# brick_i2c_gyro_l3gd20.net
KiCad netlist of a schematic drawn in EAGLE
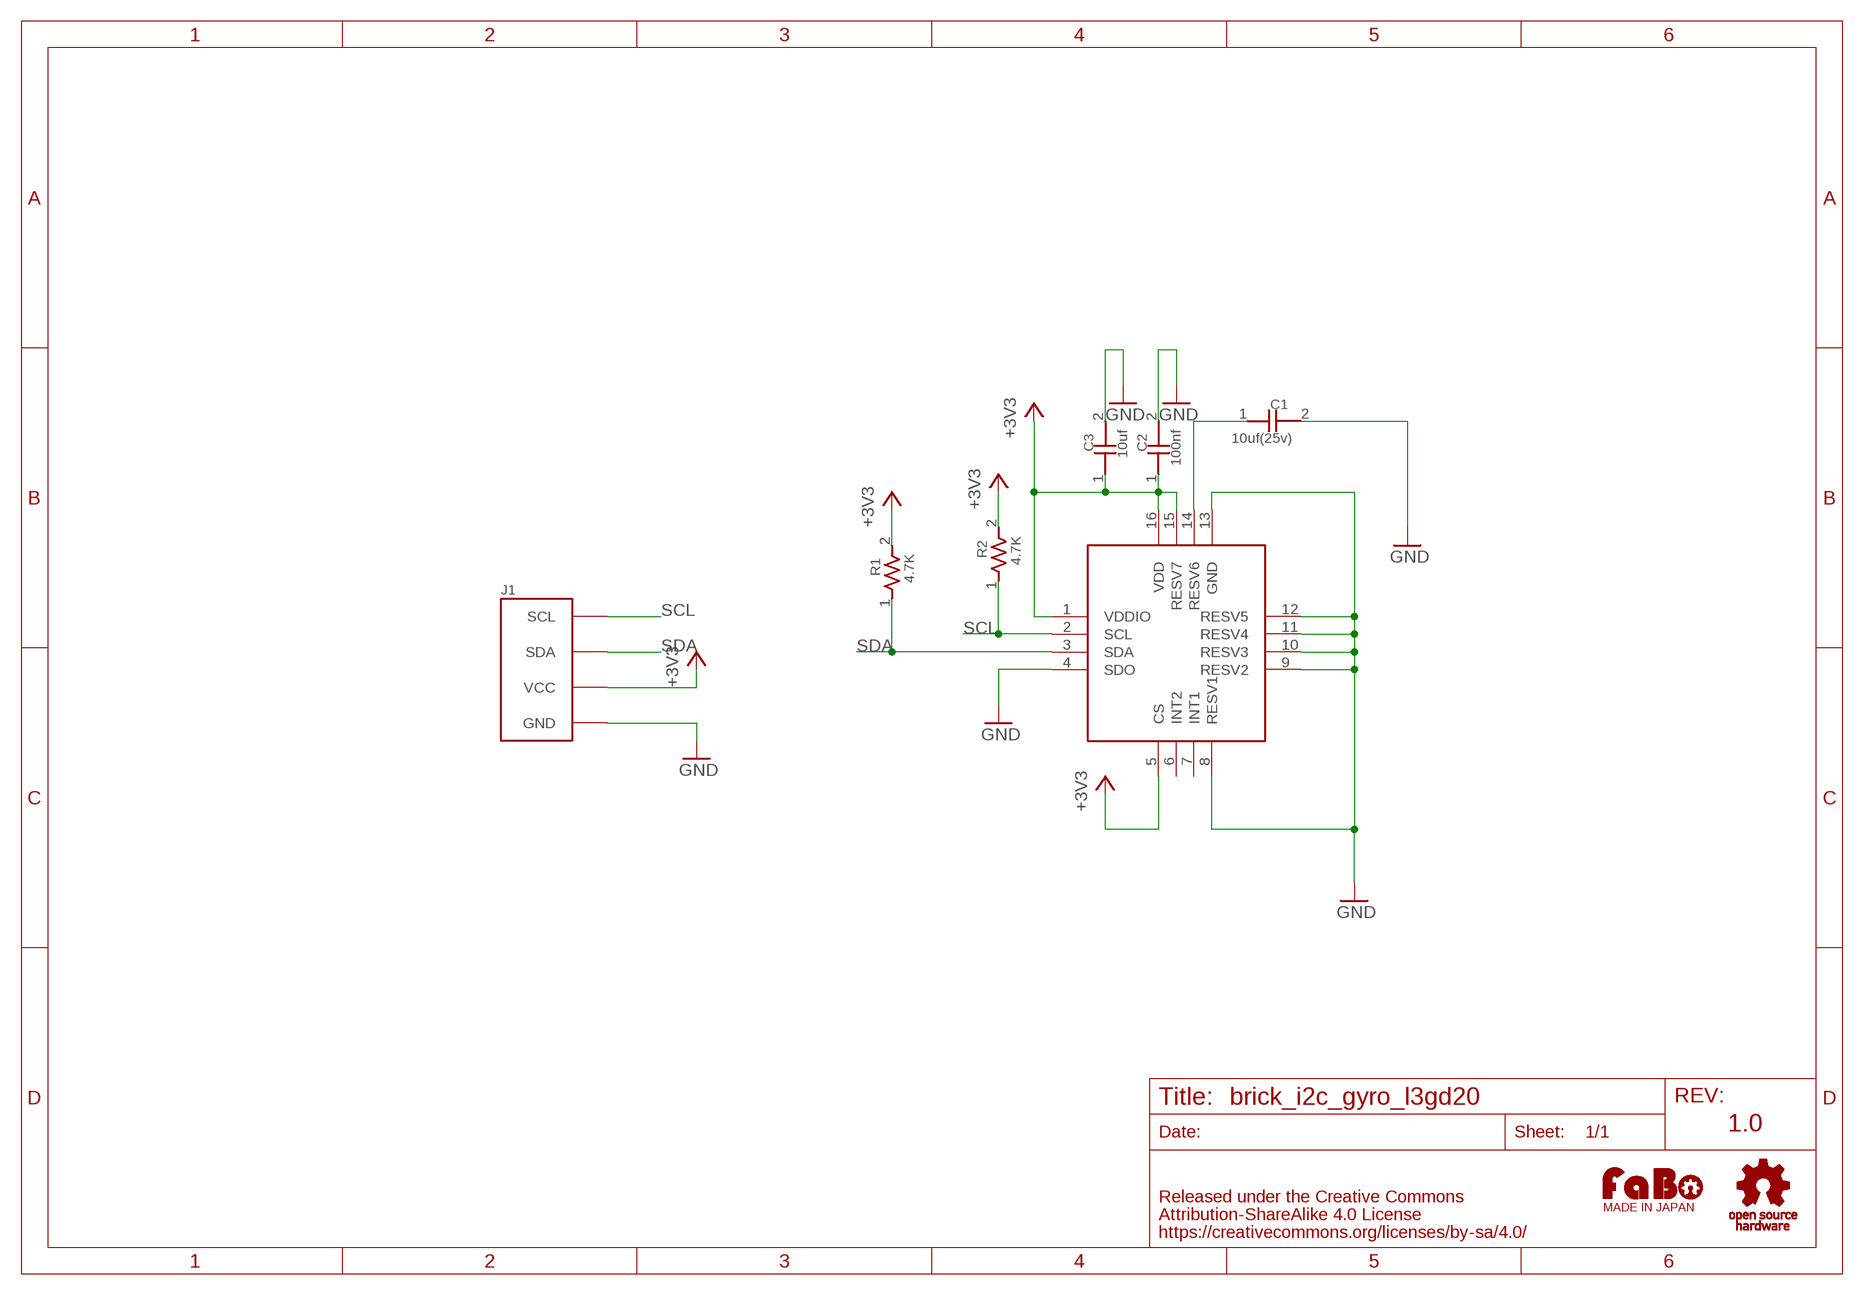
[diagram p0: schematic, sheet 1]

(export (version "E")
  (design (tool "Eeschema 10.0.6"))
  (components
    (comp (ref "C1")
      (value "10uf(25v)")
      (footprint "eagle-import:0603")
      (libsource (lib "eagle-import") (part "CAPACITOR0603"))
    )
    (comp (ref "C2")
      (value "100nf")
      (footprint "eagle-import:0603")
      (libsource (lib "eagle-import") (part "CAPACITOR0603"))
    )
    (comp (ref "C3")
      (value "10uf")
      (footprint "eagle-import:0603")
      (libsource (lib "eagle-import") (part "CAPACITOR0603"))
    )
    (comp (ref "J1")
      (value "BRICK_I2C")
      (footprint "eagle-import:BRICK_I2C")
      (libsource (lib "eagle-import") (part "BRICK_I2C"))
    )
    (comp (ref "R1")
      (value "4.7K")
      (footprint "eagle-import:0603")
      (libsource (lib "eagle-import") (part "RESISTOR0603"))
    )
    (comp (ref "R2")
      (value "4.7K")
      (footprint "eagle-import:0603")
      (libsource (lib "eagle-import") (part "RESISTOR0603"))
    )
    (comp (ref "U$1")
      (value "LOGO_OSHW_T-M")
      (footprint "eagle-import:LOGO_OSHW_T_M")
      (libsource (lib "eagle-import") (part "LOGO_OSHW_T-M"))
    )
    (comp (ref "U$3")
      (value "ST-L3GD20")
      (footprint "eagle-import:LGA-16")
      (libsource (lib "eagle-import") (part "ST-L3GD20"))
    )
    (comp (ref "U$4")
      (value "LOGO_FABO-M")
      (footprint "eagle-import:LOGO_FABO_M")
      (libsource (lib "eagle-import") (part "LOGO_FABO-M"))
    )
  )
  (nets
    (net (code "1") (name "+3V3") (class "Default")
      (node (ref "C2") (pin "1") (pinfunction "1_1") (pintype "passive"))
      (node (ref "C3") (pin "1") (pinfunction "1_1") (pintype "passive"))
      (node (ref "J1") (pin "VCC") (pinfunction "VCC_VCC") (pintype "bidirectional"))
      (node (ref "R1") (pin "2") (pinfunction "2_2") (pintype "passive"))
      (node (ref "R2") (pin "2") (pinfunction "2_2") (pintype "passive"))
      (node (ref "U$3") (pin "1") (pinfunction "VDDIO_1") (pintype "bidirectional"))
      (node (ref "U$3") (pin "15") (pinfunction "RESV7_15") (pintype "bidirectional"))
      (node (ref "U$3") (pin "16") (pinfunction "VDD_16") (pintype "bidirectional"))
      (node (ref "U$3") (pin "5") (pinfunction "CS_5") (pintype "bidirectional"))
    )
    (net (code "2") (name "/SCL") (class "Default")
      (node (ref "J1") (pin "SCL") (pinfunction "SCL_SCL") (pintype "bidirectional"))
      (node (ref "R2") (pin "1") (pinfunction "1_1") (pintype "passive"))
      (node (ref "U$3") (pin "2") (pinfunction "SCL_2") (pintype "bidirectional"))
    )
    (net (code "3") (name "/SDA") (class "Default")
      (node (ref "J1") (pin "SDA") (pinfunction "SDA_SDA") (pintype "bidirectional"))
      (node (ref "R1") (pin "1") (pinfunction "1_1") (pintype "passive"))
      (node (ref "U$3") (pin "3") (pinfunction "SDA_3") (pintype "bidirectional"))
    )
    (net (code "4") (name "GND") (class "Default")
      (node (ref "C1") (pin "2") (pinfunction "2_2") (pintype "passive"))
      (node (ref "C2") (pin "2") (pinfunction "2_2") (pintype "passive"))
      (node (ref "C3") (pin "2") (pinfunction "2_2") (pintype "passive"))
      (node (ref "J1") (pin "GND") (pinfunction "GND_GND") (pintype "bidirectional"))
      (node (ref "U$3") (pin "10") (pinfunction "RESV3_10") (pintype "bidirectional"))
      (node (ref "U$3") (pin "11") (pinfunction "RESV4_11") (pintype "bidirectional"))
      (node (ref "U$3") (pin "12") (pinfunction "RESV5_12") (pintype "bidirectional"))
      (node (ref "U$3") (pin "13") (pinfunction "GND_13") (pintype "bidirectional"))
      (node (ref "U$3") (pin "4") (pinfunction "SDO_4") (pintype "bidirectional"))
      (node (ref "U$3") (pin "8") (pinfunction "RESV1_8") (pintype "bidirectional"))
      (node (ref "U$3") (pin "9") (pinfunction "RESV2_9") (pintype "bidirectional"))
    )
    (net (code "5") (name "Net-(U$3-RESV6)") (class "Default")
      (node (ref "C1") (pin "1") (pinfunction "1_1") (pintype "passive"))
      (node (ref "U$3") (pin "14") (pinfunction "RESV6_14") (pintype "bidirectional"))
    )
    (net (code "6") (name "unconnected-(U$3-INT1-Pad7)") (class "Default")
      (node (ref "U$3") (pin "7") (pinfunction "INT1_7") (pintype "bidirectional"))
    )
    (net (code "7") (name "unconnected-(U$3-INT2-Pad6)") (class "Default")
      (node (ref "U$3") (pin "6") (pinfunction "INT2_6") (pintype "bidirectional"))
    )
  )
)
